# Little-Wire.net
KiCad netlist of a schematic drawn in EAGLE
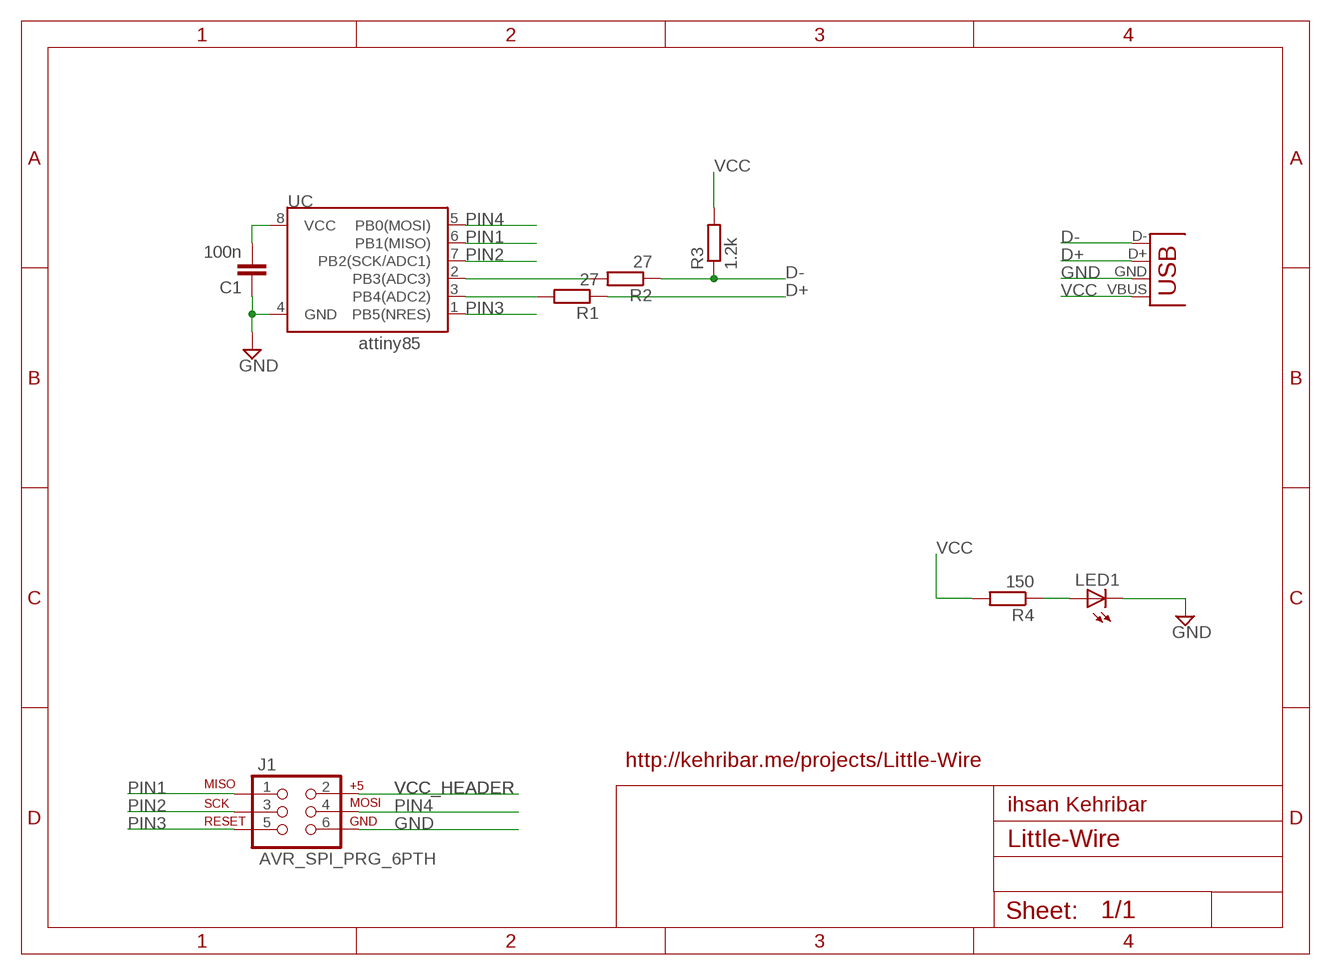
[diagram p0: schematic, sheet 1]

(export (version "E")
  (design (tool "Eeschema 10.0.6"))
  (components
    (comp (ref "C1")
      (value "100n")
      (footprint "eagle-import:C025-025X050")
      (libsource (lib "eagle-import") (part "C-EU025-025X050"))
    )
    (comp (ref "J1")
      (value "AVR_SPI_PRG_6PTH")
      (footprint "eagle-import:2X3")
      (libsource (lib "eagle-import") (part "AVR_SPI_PRG_6PTH"))
    )
    (comp (ref "LED1")
      (value "LED3MM")
      (footprint "eagle-import:LED3MM")
      (libsource (lib "eagle-import") (part "LED3MM"))
    )
    (comp (ref "R1")
      (value "27")
      (footprint "eagle-import:0204_5")
      (libsource (lib "eagle-import") (part "R-EU_0204/5"))
    )
    (comp (ref "R2")
      (value "27")
      (footprint "eagle-import:0204_5")
      (libsource (lib "eagle-import") (part "R-EU_0204/5"))
    )
    (comp (ref "R3")
      (value "1.2k")
      (footprint "eagle-import:0204_5")
      (libsource (lib "eagle-import") (part "R-EU_0204/5"))
    )
    (comp (ref "R4")
      (value "150")
      (footprint "eagle-import:0204_5")
      (libsource (lib "eagle-import") (part "R-EU_0204/5"))
    )
    (comp (ref "UC")
      (value "ATTINY45DIP8")
      (footprint "eagle-import:DIP08")
      (libsource (lib "eagle-import") (part "ATTINY45DIP8"))
    )
    (comp (ref "X1")
      (value "USB-A-H")
      (footprint "eagle-import:USB-A-H")
      (libsource (lib "eagle-import") (part "USB-A-H"))
    )
  )
  (nets
    (net (code "1") (name "/D+") (class "Default")
      (node (ref "R1") (pin "1") (pinfunction "1_1") (pintype "passive"))
      (node (ref "X1") (pin "D+") (pinfunction "D-_D+") (pintype "bidirectional"))
    )
    (net (code "2") (name "/D-") (class "Default")
      (node (ref "R2") (pin "1") (pinfunction "1_1") (pintype "passive"))
      (node (ref "R3") (pin "1") (pinfunction "1_1") (pintype "passive"))
      (node (ref "X1") (pin "D-") (pinfunction "D+_D-") (pintype "bidirectional"))
    )
    (net (code "3") (name "/PIN1") (class "Default")
      (node (ref "J1") (pin "1") (pinfunction "1_1") (pintype "passive"))
      (node (ref "UC") (pin "6") (pinfunction "PB1(MISO)_6") (pintype "bidirectional"))
    )
    (net (code "4") (name "/PIN2") (class "Default")
      (node (ref "J1") (pin "3") (pinfunction "3_3") (pintype "passive"))
      (node (ref "UC") (pin "7") (pinfunction "PB2(SCK/ADC1)_7") (pintype "bidirectional"))
    )
    (net (code "5") (name "/PIN3") (class "Default")
      (node (ref "J1") (pin "5") (pinfunction "5_5") (pintype "passive"))
      (node (ref "UC") (pin "1") (pinfunction "PB5(NRES)_1") (pintype "bidirectional"))
    )
    (net (code "6") (name "/PIN4") (class "Default")
      (node (ref "J1") (pin "4") (pinfunction "4_4") (pintype "passive"))
      (node (ref "UC") (pin "5") (pinfunction "PB0(MOSI)_5") (pintype "bidirectional"))
    )
    (net (code "7") (name "/VCC") (class "Default")
      (node (ref "C1") (pin "2") (pinfunction "2_2") (pintype "passive"))
      (node (ref "R3") (pin "2") (pinfunction "2_2") (pintype "passive"))
      (node (ref "R4") (pin "2") (pinfunction "2_2") (pintype "passive"))
      (node (ref "UC") (pin "8") (pinfunction "VCC_8") (pintype "bidirectional"))
      (node (ref "X1") (pin "VBUS") (pinfunction "GND_VBUS") (pintype "bidirectional"))
    )
    (net (code "8") (name "/VCC_HEADER") (class "Default")
      (node (ref "J1") (pin "2") (pinfunction "2_2") (pintype "passive"))
    )
    (net (code "9") (name "GND") (class "Default")
      (node (ref "C1") (pin "1") (pinfunction "1_1") (pintype "passive"))
      (node (ref "J1") (pin "6") (pinfunction "6_6") (pintype "passive"))
      (node (ref "LED1") (pin "K") (pinfunction "C_K") (pintype "passive"))
      (node (ref "UC") (pin "4") (pinfunction "GND_4") (pintype "bidirectional"))
      (node (ref "X1") (pin "GND") (pinfunction "VBUS_GND") (pintype "bidirectional"))
    )
    (net (code "10") (name "Net-(LED1-PadA)") (class "Default")
      (node (ref "LED1") (pin "A") (pinfunction "A_A") (pintype "passive"))
      (node (ref "R4") (pin "1") (pinfunction "1_1") (pintype "passive"))
    )
    (net (code "11") (name "Net-(UC-PB3(ADC3))") (class "Default")
      (node (ref "R2") (pin "2") (pinfunction "2_2") (pintype "passive"))
      (node (ref "UC") (pin "2") (pinfunction "PB3(ADC3)_2") (pintype "bidirectional"))
    )
    (net (code "12") (name "Net-(UC-PB4(ADC2))") (class "Default")
      (node (ref "R1") (pin "2") (pinfunction "2_2") (pintype "passive"))
      (node (ref "UC") (pin "3") (pinfunction "PB4(ADC2)_3") (pintype "bidirectional"))
    )
  )
)
